# p1-001.net
KiCad netlist of a schematic drawn in EAGLE
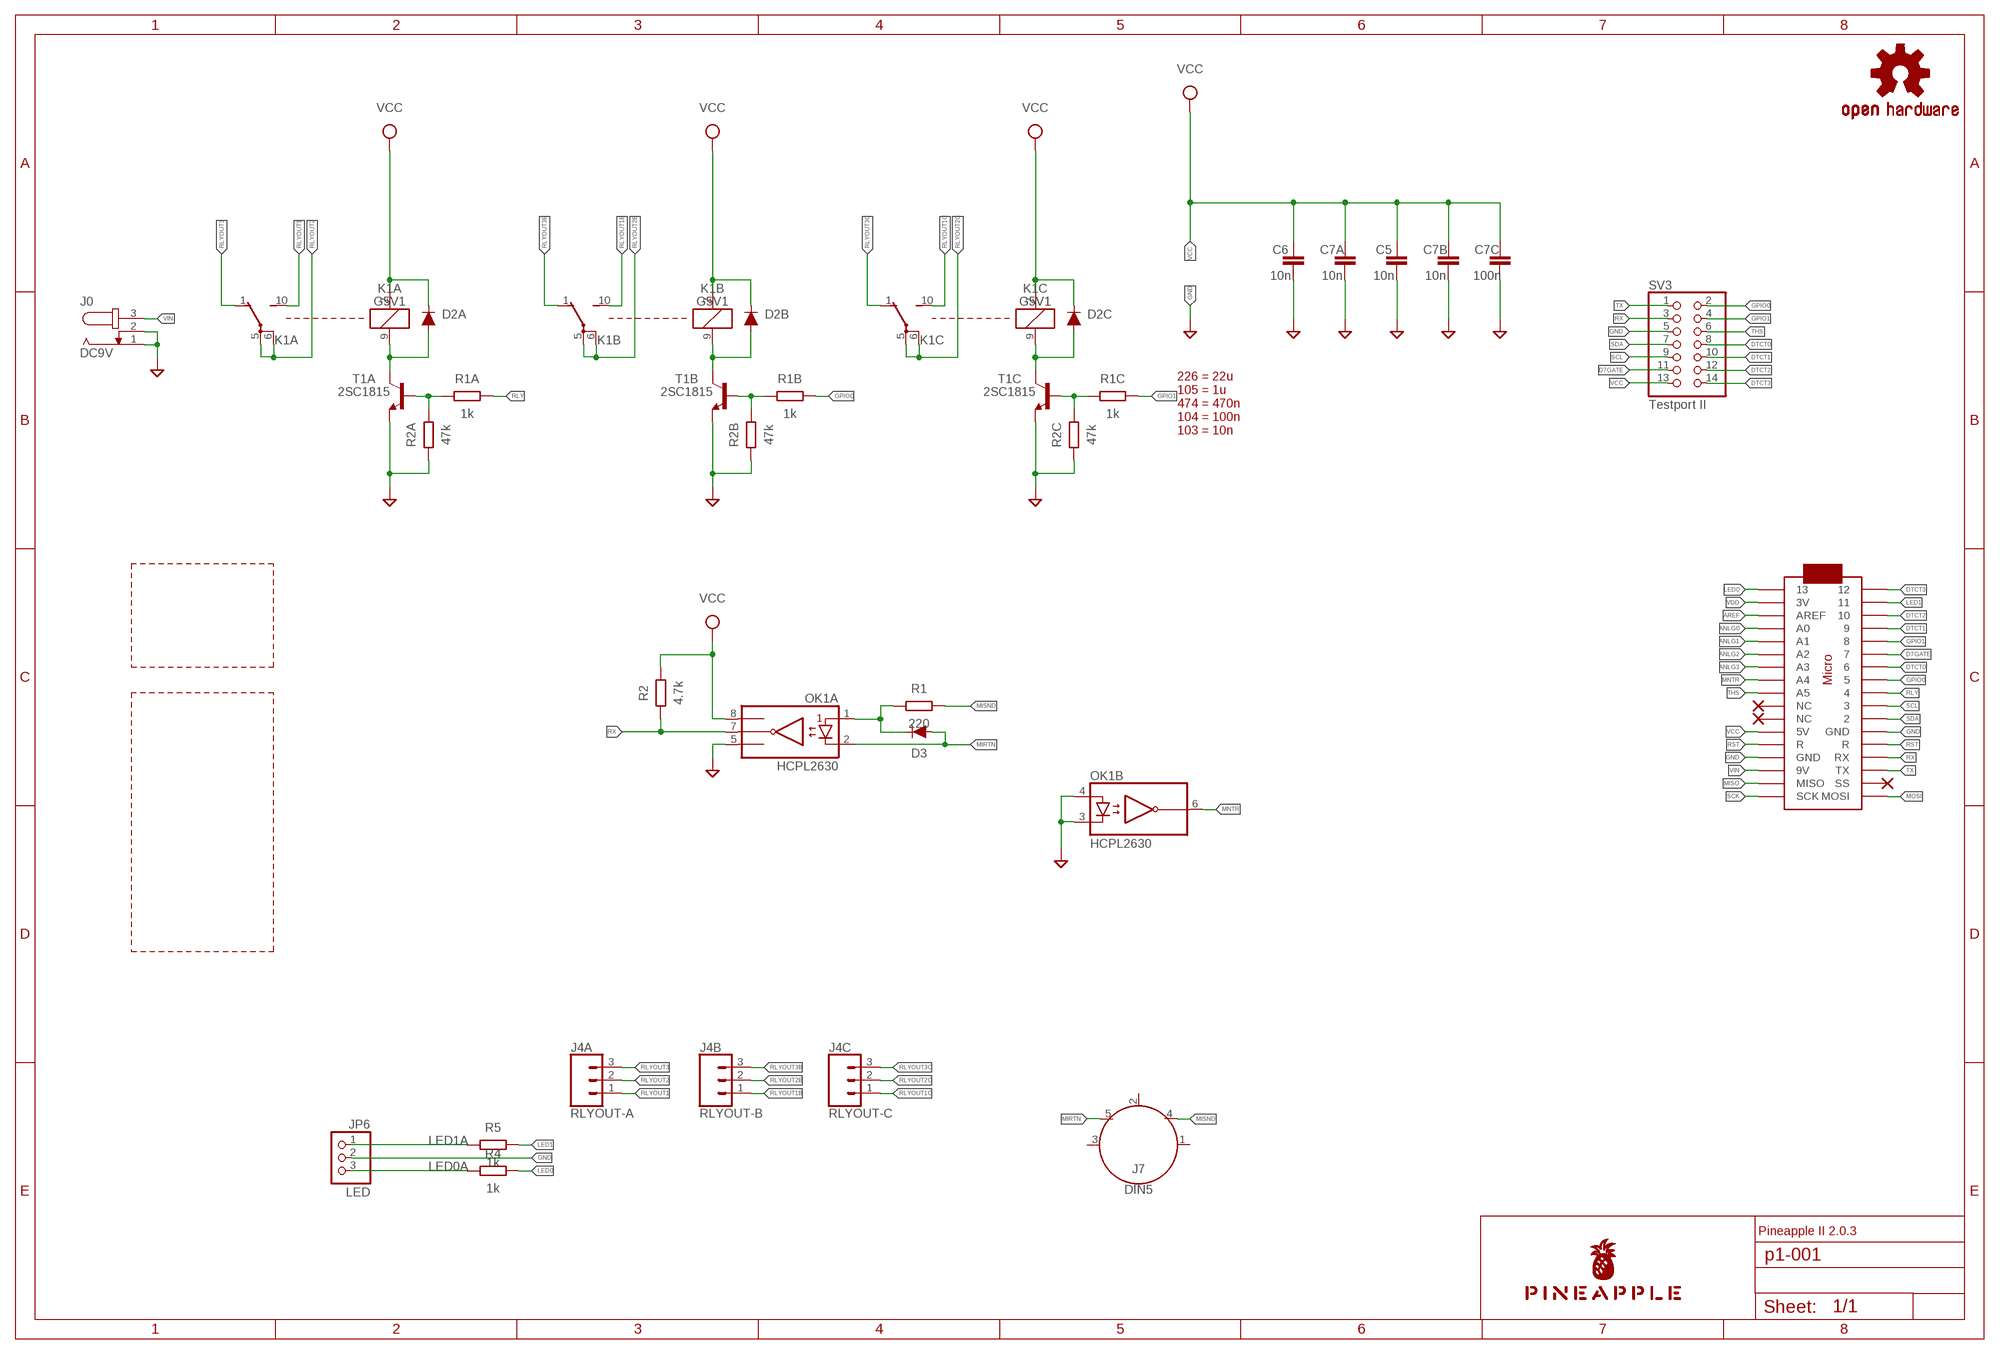
[diagram p0: schematic, sheet 1]

(export (version "E")
  (design (tool "Eeschema 10.0.6"))
  (components
    (comp (ref "C5")
      (value "10n")
      (footprint "eagle-import:C025-024X044")
      (libsource (lib "eagle-import") (part "C-EU025-024X044"))
    )
    (comp (ref "C6")
      (value "10n")
      (footprint "eagle-import:C025-024X044")
      (libsource (lib "eagle-import") (part "C-EU025-024X044"))
    )
    (comp (ref "C7A")
      (value "10n")
      (footprint "eagle-import:C025-024X044")
      (libsource (lib "eagle-import") (part "C-EU025-024X044"))
    )
    (comp (ref "C7B")
      (value "10n")
      (footprint "eagle-import:C025-024X044")
      (libsource (lib "eagle-import") (part "C-EU025-024X044"))
    )
    (comp (ref "C7C")
      (value "100n")
      (footprint "eagle-import:C025-024X044")
      (libsource (lib "eagle-import") (part "C-EU025-024X044"))
    )
    (comp (ref "D2A")
      (value "DIODE-1N4148")
      (footprint "eagle-import:DIODE-1N4148")
      (libsource (lib "eagle-import") (part "DIODE-1N4148"))
    )
    (comp (ref "D2B")
      (value "DIODE-1N4148")
      (footprint "eagle-import:DIODE-1N4148")
      (libsource (lib "eagle-import") (part "DIODE-1N4148"))
    )
    (comp (ref "D2C")
      (value "DIODE-1N4148")
      (footprint "eagle-import:DIODE-1N4148")
      (libsource (lib "eagle-import") (part "DIODE-1N4148"))
    )
    (comp (ref "D3")
      (value "DIODE-1N4148")
      (footprint "eagle-import:DIODE-1N4148")
      (libsource (lib "eagle-import") (part "DIODE-1N4148"))
    )
    (comp (ref "J0")
      (value "DC9V")
      (footprint "eagle-import:SPC4077")
      (libsource (lib "eagle-import") (part "JACK-PLUG0"))
    )
    (comp (ref "J4A")
      (value "RLYOUT-A")
      (footprint "eagle-import:JST-3-PTH")
      (libsource (lib "eagle-import") (part "CONN_03JST-PTH"))
    )
    (comp (ref "J4B")
      (value "RLYOUT-B")
      (footprint "eagle-import:JST-3-PTH")
      (libsource (lib "eagle-import") (part "CONN_03JST-PTH"))
    )
    (comp (ref "J4C")
      (value "RLYOUT-C")
      (footprint "eagle-import:JST-3-PTH")
      (libsource (lib "eagle-import") (part "CONN_03JST-PTH"))
    )
    (comp (ref "J7")
      (value "DIN5")
      (footprint "eagle-import:DIN5-RA-PTH")
      (libsource (lib "eagle-import") (part "DIN5"))
    )
    (comp (ref "JP6")
      (value "LED")
      (footprint "eagle-import:1X03")
      (libsource (lib "eagle-import") (part "PINHD-1X3"))
    )
    (comp (ref "K1A")
      (value "G5V1")
      (footprint "eagle-import:G5V1")
      (fields (field (name "MPN") "G5V-1-DC24"))
      (libsource (lib "eagle-import") (part "G5V1"))
    )
    (comp (ref "K1B")
      (value "G5V1")
      (footprint "eagle-import:G5V1")
      (fields (field (name "MPN") "G5V-1-DC24"))
      (libsource (lib "eagle-import") (part "G5V1"))
    )
    (comp (ref "K1C")
      (value "G5V1")
      (footprint "eagle-import:G5V1")
      (fields (field (name "MPN") "G5V-1-DC24"))
      (libsource (lib "eagle-import") (part "G5V1"))
    )
    (comp (ref "LOGO1")
      (value "OSHW-LOGOS-COPPER")
      (footprint "eagle-import:OSHW-LOGO-S_COPPER")
      (libsource (lib "eagle-import") (part "OSHW-LOGOS-COPPER"))
    )
    (comp (ref "MC1")
      (value "ARDUINOMICRO")
      (footprint "eagle-import:ARDUINOMICRO")
      (libsource (lib "eagle-import") (part "ARDUINOMICRO"))
    )
    (comp (ref "OK1")
      (value "HCPL2630")
      (footprint "eagle-import:DIL08")
      (fields (field (name "MF") "AGILENT TECHNOLOGIES") (field (name "MPN") "HCPL-2630-000E"))
      (libsource (lib "eagle-import") (part "HCPL2630"))
    )
    (comp (ref "R1")
      (value "220")
      (footprint "eagle-import:0204_5")
      (libsource (lib "eagle-import") (part "R-EU_0204/5"))
    )
    (comp (ref "R1A")
      (value "1k")
      (footprint "eagle-import:0204_5")
      (libsource (lib "eagle-import") (part "R-EU_0204/5"))
    )
    (comp (ref "R1B")
      (value "1k")
      (footprint "eagle-import:0204_5")
      (libsource (lib "eagle-import") (part "R-EU_0204/5"))
    )
    (comp (ref "R1C")
      (value "1k")
      (footprint "eagle-import:0204_5")
      (libsource (lib "eagle-import") (part "R-EU_0204/5"))
    )
    (comp (ref "R2")
      (value "4.7k")
      (footprint "eagle-import:0204_5")
      (libsource (lib "eagle-import") (part "R-EU_0204/5"))
    )
    (comp (ref "R2A")
      (value "47k")
      (footprint "eagle-import:0204_5")
      (libsource (lib "eagle-import") (part "R-EU_0204/5"))
    )
    (comp (ref "R2B")
      (value "47k")
      (footprint "eagle-import:0204_5")
      (libsource (lib "eagle-import") (part "R-EU_0204/5"))
    )
    (comp (ref "R2C")
      (value "47k")
      (footprint "eagle-import:0204_5")
      (libsource (lib "eagle-import") (part "R-EU_0204/5"))
    )
    (comp (ref "R4")
      (value "1k")
      (footprint "eagle-import:0204_5")
      (libsource (lib "eagle-import") (part "R-EU_0204/5"))
    )
    (comp (ref "R5")
      (value "1k")
      (footprint "eagle-import:0204_5")
      (libsource (lib "eagle-import") (part "R-EU_0204/5"))
    )
    (comp (ref "SV3")
      (value "Testport II")
      (footprint "eagle-import:2X07")
      (libsource (lib "eagle-import") (part "PINHD-2X7"))
    )
    (comp (ref "T1A")
      (value "2SC1815")
      (footprint "eagle-import:TO92-ECB")
      (libsource (lib "eagle-import") (part "2SC1815"))
    )
    (comp (ref "T1B")
      (value "2SC1815")
      (footprint "eagle-import:TO92-ECB")
      (libsource (lib "eagle-import") (part "2SC1815"))
    )
    (comp (ref "T1C")
      (value "2SC1815")
      (footprint "eagle-import:TO92-ECB")
      (libsource (lib "eagle-import") (part "2SC1815"))
    )
    (comp (ref "U$1")
      (value "PINEAPPLE450_SILK")
      (footprint "eagle-import:PINEAPPLE450_SILK")
      (libsource (lib "eagle-import") (part "PINEAPPLE450_SILK"))
    )
  )
  (nets
    (net (code "1") (name "/LED0A") (class "Default")
      (node (ref "JP6") (pin "3") (pinfunction "3_3") (pintype "passive"))
      (node (ref "R4") (pin "1") (pinfunction "1_1") (pintype "passive"))
    )
    (net (code "2") (name "/LED1A") (class "Default")
      (node (ref "JP6") (pin "1") (pinfunction "1_1") (pintype "passive"))
      (node (ref "R5") (pin "1") (pinfunction "1_1") (pintype "passive"))
    )
    (net (code "3") (name "ANLG0") (class "Default")
      (node (ref "MC1") (pin "P$31") (pinfunction "A0_P$31") (pintype "bidirectional"))
    )
    (net (code "4") (name "ANLG1") (class "Default")
      (node (ref "MC1") (pin "P$30") (pinfunction "A1_P$30") (pintype "bidirectional"))
    )
    (net (code "5") (name "ANLG2") (class "Default")
      (node (ref "MC1") (pin "P$29") (pinfunction "A2_P$29") (pintype "bidirectional"))
    )
    (net (code "6") (name "ANLG3") (class "Default")
      (node (ref "MC1") (pin "P$28") (pinfunction "A3_P$28") (pintype "bidirectional"))
    )
    (net (code "7") (name "AREF") (class "Default")
      (node (ref "MC1") (pin "P$32") (pinfunction "AREF_P$32") (pintype "bidirectional"))
    )
    (net (code "8") (name "D7GATE") (class "Default")
      (node (ref "MC1") (pin "P$6") (pinfunction "7_P$6") (pintype "bidirectional"))
      (node (ref "SV3") (pin "11") (pinfunction "11_11") (pintype "passive"))
    )
    (net (code "9") (name "DTCT0") (class "Default")
      (node (ref "MC1") (pin "P$7") (pinfunction "6_P$7") (pintype "bidirectional"))
      (node (ref "SV3") (pin "8") (pinfunction "8_8") (pintype "passive"))
    )
    (net (code "10") (name "DTCT1") (class "Default")
      (node (ref "MC1") (pin "P$4") (pinfunction "9_P$4") (pintype "bidirectional"))
      (node (ref "SV3") (pin "10") (pinfunction "10_10") (pintype "passive"))
    )
    (net (code "11") (name "DTCT2") (class "Default")
      (node (ref "MC1") (pin "P$3") (pinfunction "10_P$3") (pintype "bidirectional"))
      (node (ref "SV3") (pin "12") (pinfunction "12_12") (pintype "passive"))
    )
    (net (code "12") (name "DTCT3") (class "Default")
      (node (ref "MC1") (pin "P$1") (pinfunction "12_P$1") (pintype "bidirectional"))
      (node (ref "SV3") (pin "14") (pinfunction "14_14") (pintype "passive"))
    )
    (net (code "13") (name "GND") (class "Default")
      (node (ref "C5") (pin "2") (pinfunction "2_2") (pintype "passive"))
      (node (ref "C6") (pin "2") (pinfunction "2_2") (pintype "passive"))
      (node (ref "C7A") (pin "2") (pinfunction "2_2") (pintype "passive"))
      (node (ref "C7B") (pin "2") (pinfunction "2_2") (pintype "passive"))
      (node (ref "C7C") (pin "2") (pinfunction "2_2") (pintype "passive"))
      (node (ref "J0") (pin "1") (pinfunction "1_1") (pintype "passive"))
      (node (ref "J0") (pin "2") (pinfunction "2_2") (pintype "passive"))
      (node (ref "JP6") (pin "2") (pinfunction "2_2") (pintype "passive"))
      (node (ref "MC1") (pin "P$12") (pinfunction "GND_P$12") (pintype "bidirectional"))
      (node (ref "MC1") (pin "P$21") (pinfunction "GND_P$21") (pintype "bidirectional"))
      (node (ref "OK1") (pin "3") (pinfunction "C2_3") (pintype "passive"))
      (node (ref "OK1") (pin "4") (pinfunction "A2_4") (pintype "passive"))
      (node (ref "OK1") (pin "5") (pinfunction "GND_5") (pintype "passive"))
      (node (ref "R2A") (pin "1") (pinfunction "1_1") (pintype "passive"))
      (node (ref "R2B") (pin "1") (pinfunction "1_1") (pintype "passive"))
      (node (ref "R2C") (pin "1") (pinfunction "1_1") (pintype "passive"))
      (node (ref "SV3") (pin "5") (pinfunction "5_5") (pintype "passive"))
      (node (ref "T1A") (pin "E") (pinfunction "E_E") (pintype "passive"))
      (node (ref "T1B") (pin "E") (pinfunction "E_E") (pintype "passive"))
      (node (ref "T1C") (pin "E") (pinfunction "E_E") (pintype "passive"))
    )
    (net (code "14") (name "GPIO0") (class "Default")
      (node (ref "MC1") (pin "P$8") (pinfunction "5_P$8") (pintype "bidirectional"))
      (node (ref "R1B") (pin "2") (pinfunction "2_2") (pintype "passive"))
      (node (ref "SV3") (pin "2") (pinfunction "2_2") (pintype "passive"))
    )
    (net (code "15") (name "GPIO1") (class "Default")
      (node (ref "MC1") (pin "P$5") (pinfunction "8_P$5") (pintype "bidirectional"))
      (node (ref "R1C") (pin "2") (pinfunction "2_2") (pintype "passive"))
      (node (ref "SV3") (pin "4") (pinfunction "4_4") (pintype "passive"))
    )
    (net (code "16") (name "LED0") (class "Default")
      (node (ref "MC1") (pin "P$34") (pinfunction "13_P$34") (pintype "bidirectional"))
      (node (ref "R4") (pin "2") (pinfunction "2_2") (pintype "passive"))
    )
    (net (code "17") (name "LED1") (class "Default")
      (node (ref "MC1") (pin "P$2") (pinfunction "11_P$2") (pintype "bidirectional"))
      (node (ref "R5") (pin "2") (pinfunction "2_2") (pintype "passive"))
    )
    (net (code "18") (name "MIRTN") (class "Default")
      (node (ref "D3") (pin "A") (pinfunction "A_A") (pintype "passive"))
      (node (ref "J7") (pin "5") (pinfunction "5_5") (pintype "bidirectional"))
      (node (ref "OK1") (pin "2") (pinfunction "C1_2") (pintype "passive"))
    )
    (net (code "19") (name "MISND") (class "Default")
      (node (ref "J7") (pin "4") (pinfunction "4_4") (pintype "bidirectional"))
      (node (ref "R1") (pin "2") (pinfunction "2_2") (pintype "passive"))
    )
    (net (code "20") (name "MISO") (class "Default")
      (node (ref "MC1") (pin "P$19") (pinfunction "MISO_P$19") (pintype "bidirectional"))
    )
    (net (code "21") (name "MNTR") (class "Default")
      (node (ref "MC1") (pin "P$27") (pinfunction "A4_P$27") (pintype "bidirectional"))
      (node (ref "OK1") (pin "6") (pinfunction "VO2_6") (pintype "passive"))
    )
    (net (code "22") (name "MOSI") (class "Default")
      (node (ref "MC1") (pin "P$17") (pinfunction "MOSI_P$17") (pintype "bidirectional"))
    )
    (net (code "23") (name "Net-(K1AA-2)") (class "Default")
      (node (ref "D2A") (pin "A") (pinfunction "A_A") (pintype "passive"))
      (node (ref "K1A") (pin "9") (pinfunction "2_9") (pintype "passive"))
      (node (ref "T1A") (pin "C") (pinfunction "C_C") (pintype "passive"))
    )
    (net (code "24") (name "Net-(K1BA-2)") (class "Default")
      (node (ref "D2B") (pin "A") (pinfunction "A_A") (pintype "passive"))
      (node (ref "K1B") (pin "9") (pinfunction "2_9") (pintype "passive"))
      (node (ref "T1B") (pin "C") (pinfunction "C_C") (pintype "passive"))
    )
    (net (code "25") (name "Net-(K1CA-2)") (class "Default")
      (node (ref "D2C") (pin "A") (pinfunction "A_A") (pintype "passive"))
      (node (ref "K1C") (pin "9") (pinfunction "2_9") (pintype "passive"))
      (node (ref "T1C") (pin "C") (pinfunction "C_C") (pintype "passive"))
    )
    (net (code "26") (name "Net-(OK1A-A1)") (class "Default")
      (node (ref "D3") (pin "C") (pinfunction "C_C") (pintype "passive"))
      (node (ref "OK1") (pin "1") (pinfunction "A1_1") (pintype "passive"))
      (node (ref "R1") (pin "1") (pinfunction "1_1") (pintype "passive"))
    )
    (net (code "27") (name "Net-(R1A-Pad1)") (class "Default")
      (node (ref "R1A") (pin "1") (pinfunction "1_1") (pintype "passive"))
      (node (ref "R2A") (pin "2") (pinfunction "2_2") (pintype "passive"))
      (node (ref "T1A") (pin "B") (pinfunction "B_B") (pintype "passive"))
    )
    (net (code "28") (name "Net-(R1B-Pad1)") (class "Default")
      (node (ref "R1B") (pin "1") (pinfunction "1_1") (pintype "passive"))
      (node (ref "R2B") (pin "2") (pinfunction "2_2") (pintype "passive"))
      (node (ref "T1B") (pin "B") (pinfunction "B_B") (pintype "passive"))
    )
    (net (code "29") (name "Net-(R1C-Pad1)") (class "Default")
      (node (ref "R1C") (pin "1") (pinfunction "1_1") (pintype "passive"))
      (node (ref "R2C") (pin "2") (pinfunction "2_2") (pintype "passive"))
      (node (ref "T1C") (pin "B") (pinfunction "B_B") (pintype "passive"))
    )
    (net (code "30") (name "RLY") (class "Default")
      (node (ref "MC1") (pin "P$9") (pinfunction "4_P$9") (pintype "bidirectional"))
      (node (ref "R1A") (pin "2") (pinfunction "2_2") (pintype "passive"))
    )
    (net (code "31") (name "RLYOUT1") (class "Default")
      (node (ref "J4A") (pin "1") (pinfunction "1_1") (pintype "passive"))
      (node (ref "K1A") (pin "10") (pinfunction "S_10") (pintype "passive"))
    )
    (net (code "32") (name "RLYOUT1B") (class "Default")
      (node (ref "J4B") (pin "1") (pinfunction "1_1") (pintype "passive"))
      (node (ref "K1B") (pin "10") (pinfunction "S_10") (pintype "passive"))
    )
    (net (code "33") (name "RLYOUT1C") (class "Default")
      (node (ref "J4C") (pin "1") (pinfunction "1_1") (pintype "passive"))
      (node (ref "K1C") (pin "10") (pinfunction "S_10") (pintype "passive"))
    )
    (net (code "34") (name "RLYOUT2") (class "Default")
      (node (ref "J4A") (pin "2") (pinfunction "2_2") (pintype "passive"))
      (node (ref "K1A") (pin "5") (pinfunction "P_5") (pintype "passive"))
      (node (ref "K1A") (pin "6") (pinfunction "P_6") (pintype "passive"))
    )
    (net (code "35") (name "RLYOUT2B") (class "Default")
      (node (ref "J4B") (pin "2") (pinfunction "2_2") (pintype "passive"))
      (node (ref "K1B") (pin "5") (pinfunction "P_5") (pintype "passive"))
      (node (ref "K1B") (pin "6") (pinfunction "P_6") (pintype "passive"))
    )
    (net (code "36") (name "RLYOUT2C") (class "Default")
      (node (ref "J4C") (pin "2") (pinfunction "2_2") (pintype "passive"))
      (node (ref "K1C") (pin "5") (pinfunction "P_5") (pintype "passive"))
      (node (ref "K1C") (pin "6") (pinfunction "P_6") (pintype "passive"))
    )
    (net (code "37") (name "RLYOUT3") (class "Default")
      (node (ref "J4A") (pin "3") (pinfunction "3_3") (pintype "passive"))
      (node (ref "K1A") (pin "1") (pinfunction "O_1") (pintype "passive"))
    )
    (net (code "38") (name "RLYOUT3B") (class "Default")
      (node (ref "J4B") (pin "3") (pinfunction "3_3") (pintype "passive"))
      (node (ref "K1B") (pin "1") (pinfunction "O_1") (pintype "passive"))
    )
    (net (code "39") (name "RLYOUT3C") (class "Default")
      (node (ref "J4C") (pin "3") (pinfunction "3_3") (pintype "passive"))
      (node (ref "K1C") (pin "1") (pinfunction "O_1") (pintype "passive"))
    )
    (net (code "40") (name "RST") (class "Default")
      (node (ref "MC1") (pin "P$13") (pinfunction "R_P$13") (pintype "bidirectional"))
      (node (ref "MC1") (pin "P$22") (pinfunction "R_P$22") (pintype "bidirectional"))
    )
    (net (code "41") (name "RX") (class "Default")
      (node (ref "MC1") (pin "P$14") (pinfunction "RX_P$14") (pintype "bidirectional"))
      (node (ref "OK1") (pin "7") (pinfunction "VO1_7") (pintype "passive"))
      (node (ref "R2") (pin "1") (pinfunction "1_1") (pintype "passive"))
      (node (ref "SV3") (pin "3") (pinfunction "3_3") (pintype "passive"))
    )
    (net (code "42") (name "SCK") (class "Default")
      (node (ref "MC1") (pin "P$18") (pinfunction "SCK_P$18") (pintype "bidirectional"))
    )
    (net (code "43") (name "SCL") (class "Default")
      (node (ref "MC1") (pin "P$10") (pinfunction "3_P$10") (pintype "bidirectional"))
      (node (ref "SV3") (pin "9") (pinfunction "9_9") (pintype "passive"))
    )
    (net (code "44") (name "SDA") (class "Default")
      (node (ref "MC1") (pin "P$11") (pinfunction "2_P$11") (pintype "bidirectional"))
      (node (ref "SV3") (pin "7") (pinfunction "7_7") (pintype "passive"))
    )
    (net (code "45") (name "THS") (class "Default")
      (node (ref "MC1") (pin "P$26") (pinfunction "A5_P$26") (pintype "bidirectional"))
      (node (ref "SV3") (pin "6") (pinfunction "6_6") (pintype "passive"))
    )
    (net (code "46") (name "TX") (class "Default")
      (node (ref "MC1") (pin "P$15") (pinfunction "TX_P$15") (pintype "bidirectional"))
      (node (ref "SV3") (pin "1") (pinfunction "1_1") (pintype "passive"))
    )
    (net (code "47") (name "VCC") (class "Default")
      (node (ref "C5") (pin "1") (pinfunction "1_1") (pintype "passive"))
      (node (ref "C6") (pin "1") (pinfunction "1_1") (pintype "passive"))
      (node (ref "C7A") (pin "1") (pinfunction "1_1") (pintype "passive"))
      (node (ref "C7B") (pin "1") (pinfunction "1_1") (pintype "passive"))
      (node (ref "C7C") (pin "1") (pinfunction "1_1") (pintype "passive"))
      (node (ref "D2A") (pin "C") (pinfunction "C_C") (pintype "passive"))
      (node (ref "D2B") (pin "C") (pinfunction "C_C") (pintype "passive"))
      (node (ref "D2C") (pin "C") (pinfunction "C_C") (pintype "passive"))
      (node (ref "K1A") (pin "2") (pinfunction "1_2") (pintype "passive"))
      (node (ref "K1B") (pin "2") (pinfunction "1_2") (pintype "passive"))
      (node (ref "K1C") (pin "2") (pinfunction "1_2") (pintype "passive"))
      (node (ref "MC1") (pin "P$23") (pinfunction "5V_P$23") (pintype "bidirectional"))
      (node (ref "OK1") (pin "8") (pinfunction "VCC_8") (pintype "passive"))
      (node (ref "R2") (pin "2") (pinfunction "2_2") (pintype "passive"))
      (node (ref "SV3") (pin "13") (pinfunction "13_13") (pintype "passive"))
    )
    (net (code "48") (name "VDD") (class "Default")
      (node (ref "MC1") (pin "P$33") (pinfunction "3V_P$33") (pintype "bidirectional"))
    )
    (net (code "49") (name "VIN") (class "Default")
      (node (ref "J0") (pin "3") (pinfunction "3_3") (pintype "passive"))
      (node (ref "MC1") (pin "P$20") (pinfunction "9V_P$20") (pintype "bidirectional"))
    )
    (net (code "50") (name "unconnected-(J7-Pad1)") (class "Default")
      (node (ref "J7") (pin "1") (pinfunction "1_1") (pintype "bidirectional"))
    )
    (net (code "51") (name "unconnected-(J7-Pad2)") (class "Default")
      (node (ref "J7") (pin "2") (pinfunction "2_2") (pintype "bidirectional"))
    )
    (net (code "52") (name "unconnected-(J7-Pad3)") (class "Default")
      (node (ref "J7") (pin "3") (pinfunction "3_3") (pintype "bidirectional"))
    )
    (net (code "53") (name "unconnected-(MC1-NC-PadP$24)") (class "Default")
      (node (ref "MC1") (pin "P$24") (pinfunction "NC_P$24") (pintype "bidirectional"))
    )
    (net (code "54") (name "unconnected-(MC1-NC-PadP$25)") (class "Default")
      (node (ref "MC1") (pin "P$25") (pinfunction "NC_P$25") (pintype "bidirectional"))
    )
    (net (code "55") (name "unconnected-(MC1-SS-PadP$16)") (class "Default")
      (node (ref "MC1") (pin "P$16") (pinfunction "SS_P$16") (pintype "bidirectional"))
    )
  )
)
